# Proyecto_DM.net
KiCad netlist of a schematic drawn in EasyEDA
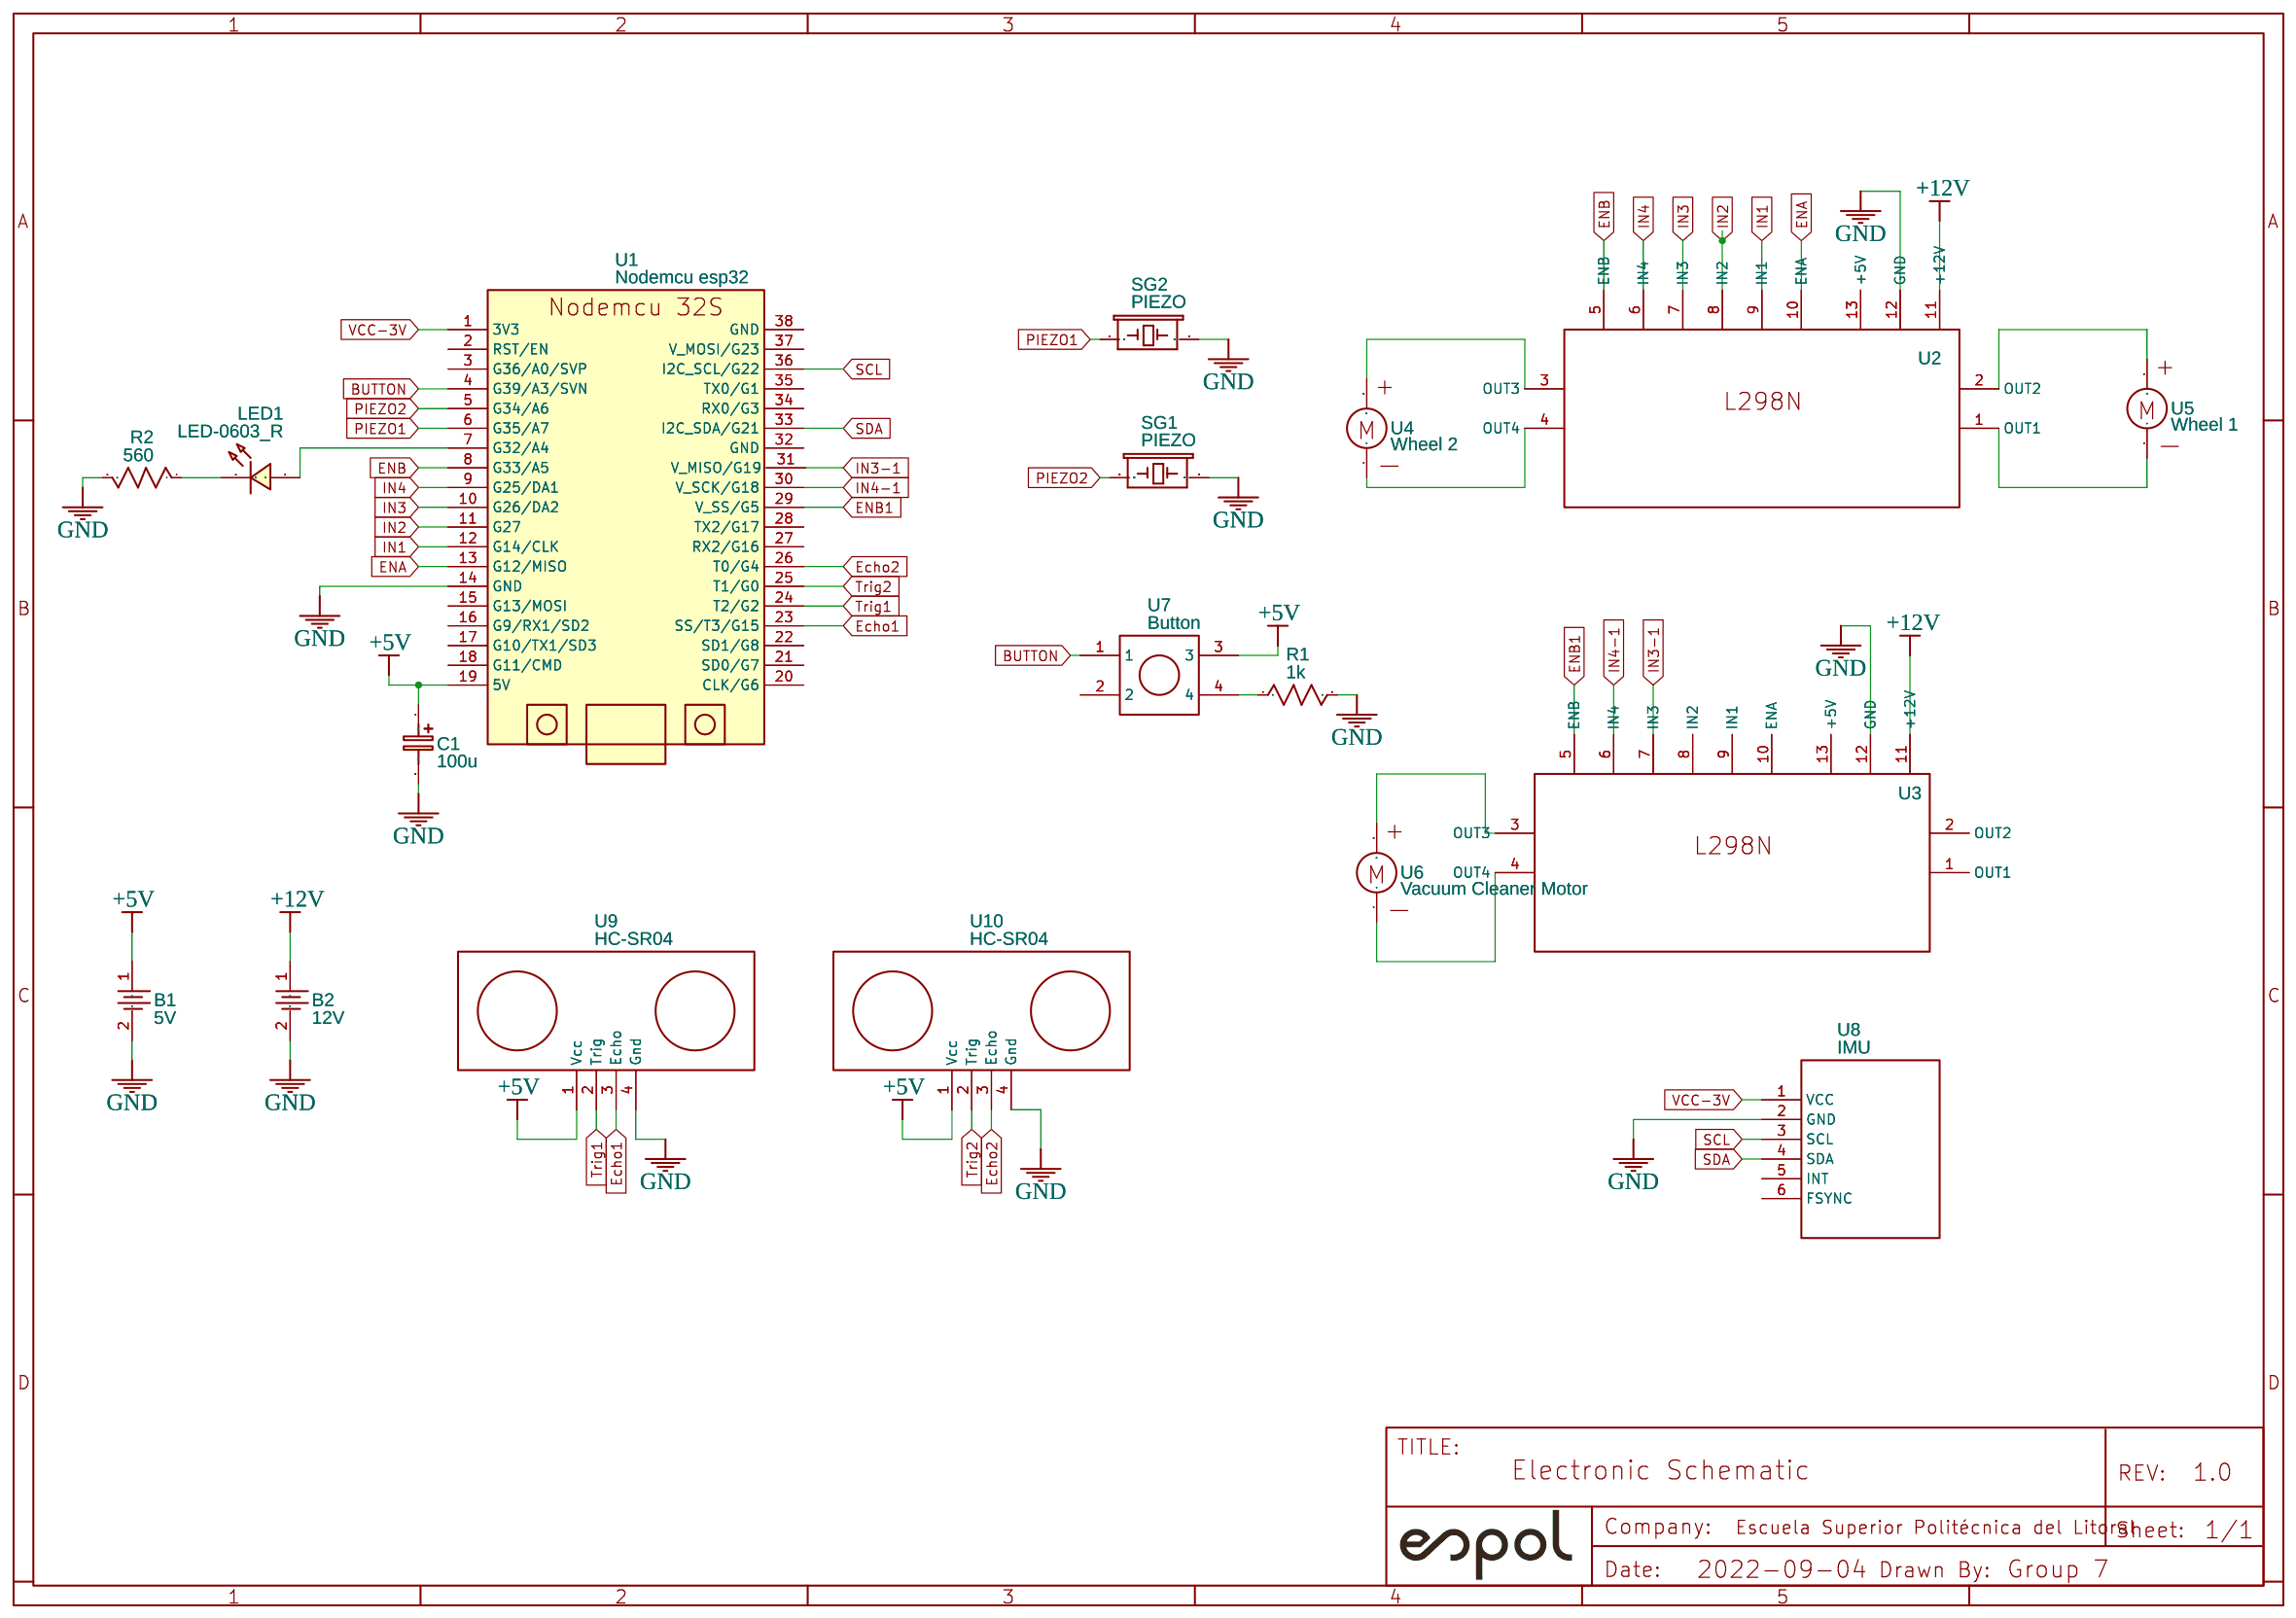
[diagram p0: schematic sheet]

(export (version "E")
  (design (tool "Eeschema 10.0.6"))
  (components
    (comp (ref "B1")
      (value "5V")
      (fields (field (name "BOM_Manufacturer Part") "CR1220-2") (field (name "BOM_Supplier Part") "C70381"))
      (libsource (lib "") (part "CR1220-2"))
    )
    (comp (ref "B2")
      (value "12V")
      (fields (field (name "BOM_Manufacturer Part") "CR1220-2") (field (name "BOM_Supplier Part") "C70381"))
      (libsource (lib "") (part "CR1220-2"))
    )
    (comp (ref "C1") (value "100u") (libsource (lib "") (part "C_Tan_SMD_A_EU")))
    (comp (ref "LED1")
      (value "LED-0603_R")
      (fields
        (field (name "BOM_Manufacturer Part") "19-217/R6C-AL1M2VY/3T")
        (field (name "BOM_Supplier Part") "C72044")
      )
      (libsource (lib "") (part "LED-0603_R"))
    )
    (comp (ref "R1") (value "1k") (libsource (lib "") (part "R_0603_US")))
    (comp (ref "R2") (value "560") (libsource (lib "") (part "R_0603_US_1")))
    (comp (ref "SG1") (value "PIEZO") (libsource (lib "") (part "PIEZO_14MM")))
    (comp (ref "SG2") (value "PIEZO") (libsource (lib "") (part "PIEZO_14MM")))
    (comp (ref "U1") (value "Nodemcu esp32") (libsource (lib "") (part "Nodemcu esp32")))
    (comp (ref "U2") (value "L298N") (libsource (lib "") (part "L298N")))
    (comp (ref "U3") (value "L298N") (libsource (lib "") (part "L298N")))
    (comp (ref "U4") (value "Wheel 2") (libsource (lib "") (part "DC Motor")))
    (comp (ref "U5") (value "Wheel 1") (libsource (lib "") (part "DC Motor")))
    (comp (ref "U6") (value "Vacuum Cleaner Motor") (libsource (lib "") (part "DC Motor")))
    (comp (ref "U7") (value "Button") (libsource (lib "") (part "12x12 Buttom")))
    (comp (ref "U8") (value "IMU") (libsource (lib "") (part "MPU9255 Modül")))
    (comp (ref "U9") (value "HC-SR04") (libsource (lib "") (part "HC-SR04")))
    (comp (ref "U10") (value "HC-SR04") (libsource (lib "") (part "HC-SR04")))
  )
  (nets
    (net (code "1") (name "+5V") (class "Default")
      (node (ref "B1") (pin "1") (pinfunction "1_1") (pintype "input"))
      (node (ref "C1") (pin "1") (pinfunction "1_1") (pintype "unspecified"))
      (node (ref "U1") (pin "19") (pinfunction "5V_19") (pintype "passive"))
      (node (ref "U10") (pin "1") (pinfunction "Vcc_1") (pintype "unspecified"))
      (node (ref "U7") (pin "3") (pinfunction "3_3") (pintype "unspecified"))
      (node (ref "U9") (pin "1") (pinfunction "Vcc_1") (pintype "unspecified"))
    )
    (net (code "2") (name "+12V") (class "Default")
      (node (ref "B2") (pin "1") (pinfunction "1_1") (pintype "input"))
      (node (ref "U2") (pin "11") (pinfunction "+12V_11") (pintype "unspecified"))
      (node (ref "U3") (pin "11") (pinfunction "+12V_11") (pintype "unspecified"))
    )
    (net (code "3") (name "BUTTON") (class "Default")
      (node (ref "U1") (pin "4") (pinfunction "G39/A3/SVN_4") (pintype "bidirectional"))
      (node (ref "U7") (pin "1") (pinfunction "1_1") (pintype "unspecified"))
    )
    (net (code "4") (name "ENA") (class "Default")
      (node (ref "U1") (pin "13") (pinfunction "G12/MISO_13") (pintype "bidirectional"))
      (node (ref "U2") (pin "10") (pinfunction "ENA_10") (pintype "unspecified"))
    )
    (net (code "5") (name "ENB") (class "Default")
      (node (ref "U1") (pin "8") (pinfunction "G33/A5_8") (pintype "bidirectional"))
      (node (ref "U2") (pin "5") (pinfunction "ENB_5") (pintype "unspecified"))
    )
    (net (code "6") (name "ENB1") (class "Default")
      (node (ref "U1") (pin "29") (pinfunction "V_SS/G5_29") (pintype "bidirectional"))
      (node (ref "U3") (pin "5") (pinfunction "ENB_5") (pintype "unspecified"))
    )
    (net (code "7") (name "Echo1") (class "Default")
      (node (ref "U1") (pin "23") (pinfunction "SS/T3/G15_23") (pintype "bidirectional"))
      (node (ref "U9") (pin "3") (pinfunction "Echo_3") (pintype "unspecified"))
    )
    (net (code "8") (name "Echo2") (class "Default")
      (node (ref "U1") (pin "26") (pinfunction "T0/G4_26") (pintype "bidirectional"))
      (node (ref "U10") (pin "3") (pinfunction "Echo_3") (pintype "unspecified"))
    )
    (net (code "9") (name "GND") (class "Default")
      (node (ref "B1") (pin "2") (pinfunction "2_2") (pintype "input"))
      (node (ref "B2") (pin "2") (pinfunction "2_2") (pintype "input"))
      (node (ref "C1") (pin "2") (pinfunction "2_2") (pintype "unspecified"))
      (node (ref "R1") (pin "2") (pinfunction "2_2") (pintype "unspecified"))
      (node (ref "R2") (pin "2") (pinfunction "2_2") (pintype "unspecified"))
      (node (ref "SG1") (pin "P$2") (pinfunction "P$2_P$2") (pintype "bidirectional"))
      (node (ref "SG2") (pin "P$2") (pinfunction "P$2_P$2") (pintype "bidirectional"))
      (node (ref "U1") (pin "14") (pinfunction "GND_14") (pintype "passive"))
      (node (ref "U10") (pin "4") (pinfunction "Gnd_4") (pintype "unspecified"))
      (node (ref "U2") (pin "12") (pinfunction "GND_12") (pintype "unspecified"))
      (node (ref "U3") (pin "12") (pinfunction "GND_12") (pintype "unspecified"))
      (node (ref "U8") (pin "2") (pinfunction "GND_2") (pintype "unspecified"))
      (node (ref "U9") (pin "4") (pinfunction "Gnd_4") (pintype "unspecified"))
    )
    (net (code "10") (name "IN1") (class "Default")
      (node (ref "U1") (pin "12") (pinfunction "G14/CLK_12") (pintype "bidirectional"))
      (node (ref "U2") (pin "9") (pinfunction "IN1_9") (pintype "unspecified"))
    )
    (net (code "11") (name "IN2") (class "Default")
      (node (ref "U1") (pin "11") (pinfunction "G27_11") (pintype "bidirectional"))
      (node (ref "U2") (pin "8") (pinfunction "IN2_8") (pintype "unspecified"))
    )
    (net (code "12") (name "IN3") (class "Default")
      (node (ref "U1") (pin "10") (pinfunction "G26/DA2_10") (pintype "bidirectional"))
      (node (ref "U2") (pin "7") (pinfunction "IN3_7") (pintype "unspecified"))
    )
    (net (code "13") (name "IN3-1") (class "Default")
      (node (ref "U1") (pin "31") (pinfunction "V_MISO/G19_31") (pintype "bidirectional"))
      (node (ref "U3") (pin "7") (pinfunction "IN3_7") (pintype "unspecified"))
    )
    (net (code "14") (name "IN4") (class "Default")
      (node (ref "U1") (pin "9") (pinfunction "G25/DA1_9") (pintype "bidirectional"))
      (node (ref "U2") (pin "6") (pinfunction "IN4_6") (pintype "unspecified"))
    )
    (net (code "15") (name "IN4-1") (class "Default")
      (node (ref "U1") (pin "30") (pinfunction "V_SCK/G18_30") (pintype "bidirectional"))
      (node (ref "U3") (pin "6") (pinfunction "IN4_6") (pintype "unspecified"))
    )
    (net (code "16") (name "Net-(LED1-Pad2)") (class "Default")
      (node (ref "LED1") (pin "2") (pinfunction "2_2") (pintype "unspecified"))
      (node (ref "R2") (pin "1") (pinfunction "1_1") (pintype "unspecified"))
    )
    (net (code "17") (name "Net-(R1-Pad1)") (class "Default")
      (node (ref "R1") (pin "1") (pinfunction "1_1") (pintype "unspecified"))
      (node (ref "U7") (pin "4") (pinfunction "4_4") (pintype "unspecified"))
    )
    (net (code "18") (name "Net-(U1-G32{slash}A4)") (class "Default")
      (node (ref "LED1") (pin "1") (pinfunction "1_1") (pintype "unspecified"))
      (node (ref "U1") (pin "7") (pinfunction "G32/A4_7") (pintype "bidirectional"))
    )
    (net (code "19") (name "Net-(U2-OUT1)") (class "Default")
      (node (ref "U2") (pin "1") (pinfunction "OUT1_1") (pintype "unspecified"))
      (node (ref "U5") (pin "1") (pinfunction "1_1") (pintype "unspecified"))
    )
    (net (code "20") (name "Net-(U2-OUT2)") (class "Default")
      (node (ref "U2") (pin "2") (pinfunction "OUT2_2") (pintype "unspecified"))
      (node (ref "U5") (pin "2") (pinfunction "2_2") (pintype "unspecified"))
    )
    (net (code "21") (name "Net-(U2-OUT3)") (class "Default")
      (node (ref "U2") (pin "3") (pinfunction "OUT3_3") (pintype "unspecified"))
      (node (ref "U4") (pin "2") (pinfunction "2_2") (pintype "unspecified"))
    )
    (net (code "22") (name "Net-(U2-OUT4)") (class "Default")
      (node (ref "U2") (pin "4") (pinfunction "OUT4_4") (pintype "unspecified"))
      (node (ref "U4") (pin "1") (pinfunction "1_1") (pintype "unspecified"))
    )
    (net (code "23") (name "Net-(U3-OUT3)") (class "Default")
      (node (ref "U3") (pin "3") (pinfunction "OUT3_3") (pintype "unspecified"))
      (node (ref "U6") (pin "2") (pinfunction "2_2") (pintype "unspecified"))
    )
    (net (code "24") (name "Net-(U3-OUT4)") (class "Default")
      (node (ref "U3") (pin "4") (pinfunction "OUT4_4") (pintype "unspecified"))
      (node (ref "U6") (pin "1") (pinfunction "1_1") (pintype "unspecified"))
    )
    (net (code "25") (name "PIEZO1") (class "Default")
      (node (ref "SG2") (pin "P$1") (pinfunction "P$1_P$1") (pintype "bidirectional"))
      (node (ref "U1") (pin "6") (pinfunction "G35/A7_6") (pintype "bidirectional"))
    )
    (net (code "26") (name "PIEZO2") (class "Default")
      (node (ref "SG1") (pin "P$1") (pinfunction "P$1_P$1") (pintype "bidirectional"))
      (node (ref "U1") (pin "5") (pinfunction "G34/A6_5") (pintype "bidirectional"))
    )
    (net (code "27") (name "SCL") (class "Default")
      (node (ref "U1") (pin "36") (pinfunction "I2C_SCL/G22_36") (pintype "bidirectional"))
      (node (ref "U8") (pin "3") (pinfunction "SCL_3") (pintype "unspecified"))
    )
    (net (code "28") (name "SDA") (class "Default")
      (node (ref "U1") (pin "33") (pinfunction "I2C_SDA/G21_33") (pintype "bidirectional"))
      (node (ref "U8") (pin "4") (pinfunction "SDA_4") (pintype "unspecified"))
    )
    (net (code "29") (name "Trig1") (class "Default")
      (node (ref "U1") (pin "24") (pinfunction "T2/G2_24") (pintype "bidirectional"))
      (node (ref "U9") (pin "2") (pinfunction "Trig_2") (pintype "unspecified"))
    )
    (net (code "30") (name "Trig2") (class "Default")
      (node (ref "U1") (pin "25") (pinfunction "T1/G0_25") (pintype "bidirectional"))
      (node (ref "U10") (pin "2") (pinfunction "Trig_2") (pintype "unspecified"))
    )
    (net (code "31") (name "VCC-3V") (class "Default")
      (node (ref "U1") (pin "1") (pinfunction "3V3_1") (pintype "passive"))
      (node (ref "U8") (pin "1") (pinfunction "VCC_1") (pintype "unspecified"))
    )
    (net (code "32") (name "unconnected-(U1-CLK{slash}G6-Pad20)") (class "Default")
      (node (ref "U1") (pin "20") (pinfunction "CLK/G6_20") (pintype "bidirectional"))
    )
    (net (code "33") (name "unconnected-(U1-G9{slash}RX1{slash}SD2-Pad16)") (class "Default")
      (node (ref "U1") (pin "16") (pinfunction "G9/RX1/SD2_16") (pintype "bidirectional"))
    )
    (net (code "34") (name "unconnected-(U1-G10{slash}TX1{slash}SD3-Pad17)") (class "Default")
      (node (ref "U1") (pin "17") (pinfunction "G10/TX1/SD3_17") (pintype "bidirectional"))
    )
    (net (code "35") (name "unconnected-(U1-G11{slash}CMD-Pad18)") (class "Default")
      (node (ref "U1") (pin "18") (pinfunction "G11/CMD_18") (pintype "bidirectional"))
    )
    (net (code "36") (name "unconnected-(U1-G13{slash}MOSI-Pad15)") (class "Default")
      (node (ref "U1") (pin "15") (pinfunction "G13/MOSI_15") (pintype "bidirectional"))
    )
    (net (code "37") (name "unconnected-(U1-G36{slash}A0{slash}SVP-Pad3)") (class "Default")
      (node (ref "U1") (pin "3") (pinfunction "G36/A0/SVP_3") (pintype "bidirectional"))
    )
    (net (code "38") (name "unconnected-(U1-GND-Pad32)") (class "Default")
      (node (ref "U1") (pin "32") (pinfunction "GND_32") (pintype "passive"))
    )
    (net (code "39") (name "unconnected-(U1-GND-Pad38)") (class "Default")
      (node (ref "U1") (pin "38") (pinfunction "GND_38") (pintype "passive"))
    )
    (net (code "40") (name "unconnected-(U1-RST{slash}EN-Pad2)") (class "Default")
      (node (ref "U1") (pin "2") (pinfunction "RST/EN_2") (pintype "bidirectional"))
    )
    (net (code "41") (name "unconnected-(U1-RX0{slash}G3-Pad34)") (class "Default")
      (node (ref "U1") (pin "34") (pinfunction "RX0/G3_34") (pintype "bidirectional"))
    )
    (net (code "42") (name "unconnected-(U1-RX2{slash}G16-Pad27)") (class "Default")
      (node (ref "U1") (pin "27") (pinfunction "RX2/G16_27") (pintype "bidirectional"))
    )
    (net (code "43") (name "unconnected-(U1-SD0{slash}G7-Pad21)") (class "Default")
      (node (ref "U1") (pin "21") (pinfunction "SD0/G7_21") (pintype "bidirectional"))
    )
    (net (code "44") (name "unconnected-(U1-SD1{slash}G8-Pad22)") (class "Default")
      (node (ref "U1") (pin "22") (pinfunction "SD1/G8_22") (pintype "bidirectional"))
    )
    (net (code "45") (name "unconnected-(U1-TX0{slash}G1-Pad35)") (class "Default")
      (node (ref "U1") (pin "35") (pinfunction "TX0/G1_35") (pintype "bidirectional"))
    )
    (net (code "46") (name "unconnected-(U1-TX2{slash}G17-Pad28)") (class "Default")
      (node (ref "U1") (pin "28") (pinfunction "TX2/G17_28") (pintype "bidirectional"))
    )
    (net (code "47") (name "unconnected-(U1-V_MOSI{slash}G23-Pad37)") (class "Default")
      (node (ref "U1") (pin "37") (pinfunction "V_MOSI/G23_37") (pintype "bidirectional"))
    )
    (net (code "48") (name "unconnected-(U2-+5V-Pad13)") (class "Default")
      (node (ref "U2") (pin "13") (pinfunction "+5V_13") (pintype "unspecified"))
    )
    (net (code "49") (name "unconnected-(U3-+5V-Pad13)") (class "Default")
      (node (ref "U3") (pin "13") (pinfunction "+5V_13") (pintype "unspecified"))
    )
    (net (code "50") (name "unconnected-(U3-ENA-Pad10)") (class "Default")
      (node (ref "U3") (pin "10") (pinfunction "ENA_10") (pintype "unspecified"))
    )
    (net (code "51") (name "unconnected-(U3-IN1-Pad9)") (class "Default")
      (node (ref "U3") (pin "9") (pinfunction "IN1_9") (pintype "unspecified"))
    )
    (net (code "52") (name "unconnected-(U3-IN2-Pad8)") (class "Default")
      (node (ref "U3") (pin "8") (pinfunction "IN2_8") (pintype "unspecified"))
    )
    (net (code "53") (name "unconnected-(U3-OUT1-Pad1)") (class "Default")
      (node (ref "U3") (pin "1") (pinfunction "OUT1_1") (pintype "unspecified"))
    )
    (net (code "54") (name "unconnected-(U3-OUT2-Pad2)") (class "Default")
      (node (ref "U3") (pin "2") (pinfunction "OUT2_2") (pintype "unspecified"))
    )
    (net (code "55") (name "unconnected-(U7-Pad2)") (class "Default")
      (node (ref "U7") (pin "2") (pinfunction "2_2") (pintype "unspecified"))
    )
    (net (code "56") (name "unconnected-(U8-FSYNC-Pad6)") (class "Default")
      (node (ref "U8") (pin "6") (pinfunction "FSYNC_6") (pintype "unspecified"))
    )
    (net (code "57") (name "unconnected-(U8-INT-Pad5)") (class "Default")
      (node (ref "U8") (pin "5") (pinfunction "INT_5") (pintype "unspecified"))
    )
  )
)
